# v2_0.net
KiCad netlist of a schematic drawn in Altium Designer
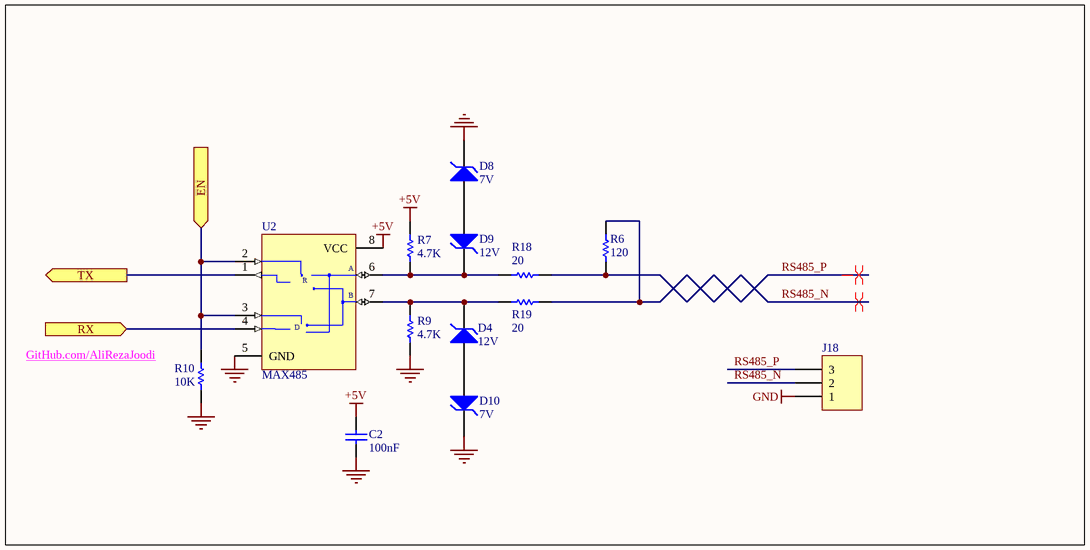
[diagram p0: v2.0.SchDoc]

(export (version "E")
  (design (tool "Eeschema 10.0.6"))
  (components
    (comp (ref "C2")
      (value "100nF")
      (footprint "CAPNTO2.54-3.05x1.78A")
      (description "Capacitor")
      (fields (field (name "MANUFACTURER") "Generic Components") (field (name "PUBLISHER") "Altium Limited"))
      (libsource (lib "Miscellaneous Devices") (part "Cap"))
    )
    (comp (ref "D4")
      (value "12V")
      (footprint "DIODE0.4_Glass")
      (description "Zener Diode")
      (fields (field (name "MANUFACTURER") "Generic Components") (field (name "PUBLISHER") "Altium Limited"))
      (libsource (lib "Miscellaneous Devices") (part "D Zener"))
    )
    (comp (ref "D8")
      (value "7V")
      (footprint "DIODE0.4_Glass")
      (description "Zener Diode")
      (fields (field (name "MANUFACTURER") "Generic Components") (field (name "PUBLISHER") "Altium Limited"))
      (libsource (lib "Miscellaneous Devices") (part "D Zener"))
    )
    (comp (ref "D9")
      (value "12V")
      (footprint "DIODE0.4_Glass")
      (description "Zener Diode")
      (fields (field (name "MANUFACTURER") "Generic Components") (field (name "PUBLISHER") "Altium Limited"))
      (libsource (lib "Miscellaneous Devices") (part "D Zener"))
    )
    (comp (ref "D10")
      (value "7V")
      (footprint "DIODE0.4_Glass")
      (description "Zener Diode")
      (fields (field (name "MANUFACTURER") "Generic Components") (field (name "PUBLISHER") "Altium Limited"))
      (libsource (lib "Miscellaneous Devices") (part "D Zener"))
    )
    (comp (ref "J18")
      (value "Header 3")
      (footprint "Fonics_3PIN_1")
      (description "Header, 3-Pin")
      (fields (field (name "MANUFACTURER") "Generic Components") (field (name "PUBLISHER") "Altium Limited"))
      (libsource (lib "Miscellaneous Connectors") (part "Header 3"))
    )
    (comp (ref "R6")
      (value "120")
      (footprint "AXIAL-0.4")
      (description "Resistor")
      (fields (field (name "PUBLISHER") "Altium Limited"))
      (libsource (lib "Miscellaneous Devices") (part "Res1"))
    )
    (comp (ref "R7")
      (value "4.7K")
      (footprint "AXIAL-0.4")
      (description "Resistor")
      (fields (field (name "PUBLISHER") "Altium Limited"))
      (libsource (lib "Miscellaneous Devices") (part "Res1"))
    )
    (comp (ref "R9")
      (value "4.7K")
      (footprint "AXIAL-0.4")
      (description "Resistor")
      (fields (field (name "PUBLISHER") "Altium Limited"))
      (libsource (lib "Miscellaneous Devices") (part "Res1"))
    )
    (comp (ref "R10")
      (value "10K")
      (footprint "AXIAL-0.4")
      (description "Resistor")
      (fields (field (name "PUBLISHER") "Altium Limited"))
      (libsource (lib "Miscellaneous Devices") (part "Res1"))
    )
    (comp (ref "R18")
      (value "20")
      (footprint "AXIAL-0.4")
      (description "Resistor")
      (fields (field (name "PUBLISHER") "Altium Limited"))
      (libsource (lib "Miscellaneous Devices") (part "Res1"))
    )
    (comp (ref "R19")
      (value "20")
      (footprint "AXIAL-0.4")
      (description "Resistor")
      (fields (field (name "PUBLISHER") "Altium Limited"))
      (libsource (lib "Miscellaneous Devices") (part "Res1"))
    )
    (comp (ref "U2")
      (value "MAX485")
      (footprint "PA8")
      (description "Low-Power, Slew-Rate-Limited RS-485/RS-422 Transceiver")
      (fields (field (name "PUBLISHER") "Altium Limited"))
      (libsource (lib "Maxim Communication Transceiver") (part "MAX485CPA"))
    )
  )
  (nets
    (net (code "1") (name "+5V") (class "Default")
      (node (ref "C2") (pin "2") (pinfunction "2_2") (pintype "passive"))
      (node (ref "R7") (pin "1") (pinfunction "1_1") (pintype "passive"))
      (node (ref "U2") (pin "8") (pinfunction "VCC_8") (pintype "power_in"))
    )
    (net (code "2") (name "/EN") (class "Default")
      (node (ref "R10") (pin "2") (pinfunction "2_2") (pintype "passive"))
      (node (ref "U2") (pin "2") (pinfunction "~{RE}_2") (pintype "input"))
      (node (ref "U2") (pin "3") (pinfunction "DE_3") (pintype "input"))
    )
    (net (code "3") (name "/RS485_N") (class "Default")
      (node (ref "J18") (pin "2") (pinfunction "2_2") (pintype "passive"))
      (node (ref "R19") (pin "1") (pinfunction "1_1") (pintype "passive"))
      (node (ref "R6") (pin "2") (pinfunction "2_2") (pintype "passive"))
    )
    (net (code "4") (name "/RS485_P") (class "Default")
      (node (ref "J18") (pin "3") (pinfunction "3_3") (pintype "passive"))
      (node (ref "R18") (pin "1") (pinfunction "1_1") (pintype "passive"))
      (node (ref "R6") (pin "1") (pinfunction "1_1") (pintype "passive"))
    )
    (net (code "5") (name "/RX") (class "Default")
      (node (ref "U2") (pin "4") (pinfunction "DI_4") (pintype "input"))
    )
    (net (code "6") (name "/TX") (class "Default")
      (node (ref "U2") (pin "1") (pinfunction "RO_1") (pintype "output"))
    )
    (net (code "7") (name "GND") (class "Default")
      (node (ref "C2") (pin "1") (pinfunction "1_1") (pintype "passive"))
      (node (ref "D10") (pin "2") (pinfunction "K_2") (pintype "passive"))
      (node (ref "D8") (pin "2") (pinfunction "K_2") (pintype "passive"))
      (node (ref "J18") (pin "1") (pinfunction "1_1") (pintype "passive"))
      (node (ref "R10") (pin "1") (pinfunction "1_1") (pintype "passive"))
      (node (ref "R9") (pin "2") (pinfunction "2_2") (pintype "passive"))
      (node (ref "U2") (pin "5") (pinfunction "GND_5") (pintype "power_in"))
    )
    (net (code "8") (name "Net-(D4-K)") (class "Default")
      (node (ref "D4") (pin "2") (pinfunction "K_2") (pintype "passive"))
      (node (ref "R19") (pin "2") (pinfunction "2_2") (pintype "passive"))
      (node (ref "R9") (pin "1") (pinfunction "1_1") (pintype "passive"))
      (node (ref "U2") (pin "7") (pinfunction "B_7") (pintype "bidirectional"))
    )
    (net (code "9") (name "Net-(D8-A)") (class "Default")
      (node (ref "D8") (pin "1") (pinfunction "A_1") (pintype "passive"))
      (node (ref "D9") (pin "1") (pinfunction "A_1") (pintype "passive"))
    )
    (net (code "10") (name "Net-(D9-K)") (class "Default")
      (node (ref "D9") (pin "2") (pinfunction "K_2") (pintype "passive"))
      (node (ref "R18") (pin "2") (pinfunction "2_2") (pintype "passive"))
      (node (ref "R7") (pin "2") (pinfunction "2_2") (pintype "passive"))
      (node (ref "U2") (pin "6") (pinfunction "A_6") (pintype "bidirectional"))
    )
    (net (code "11") (name "Net-(D10-A)") (class "Default")
      (node (ref "D10") (pin "1") (pinfunction "A_1") (pintype "passive"))
      (node (ref "D4") (pin "1") (pinfunction "A_1") (pintype "passive"))
    )
  )
)
